# VCO.net
KiCad netlist of a schematic drawn in EAGLE
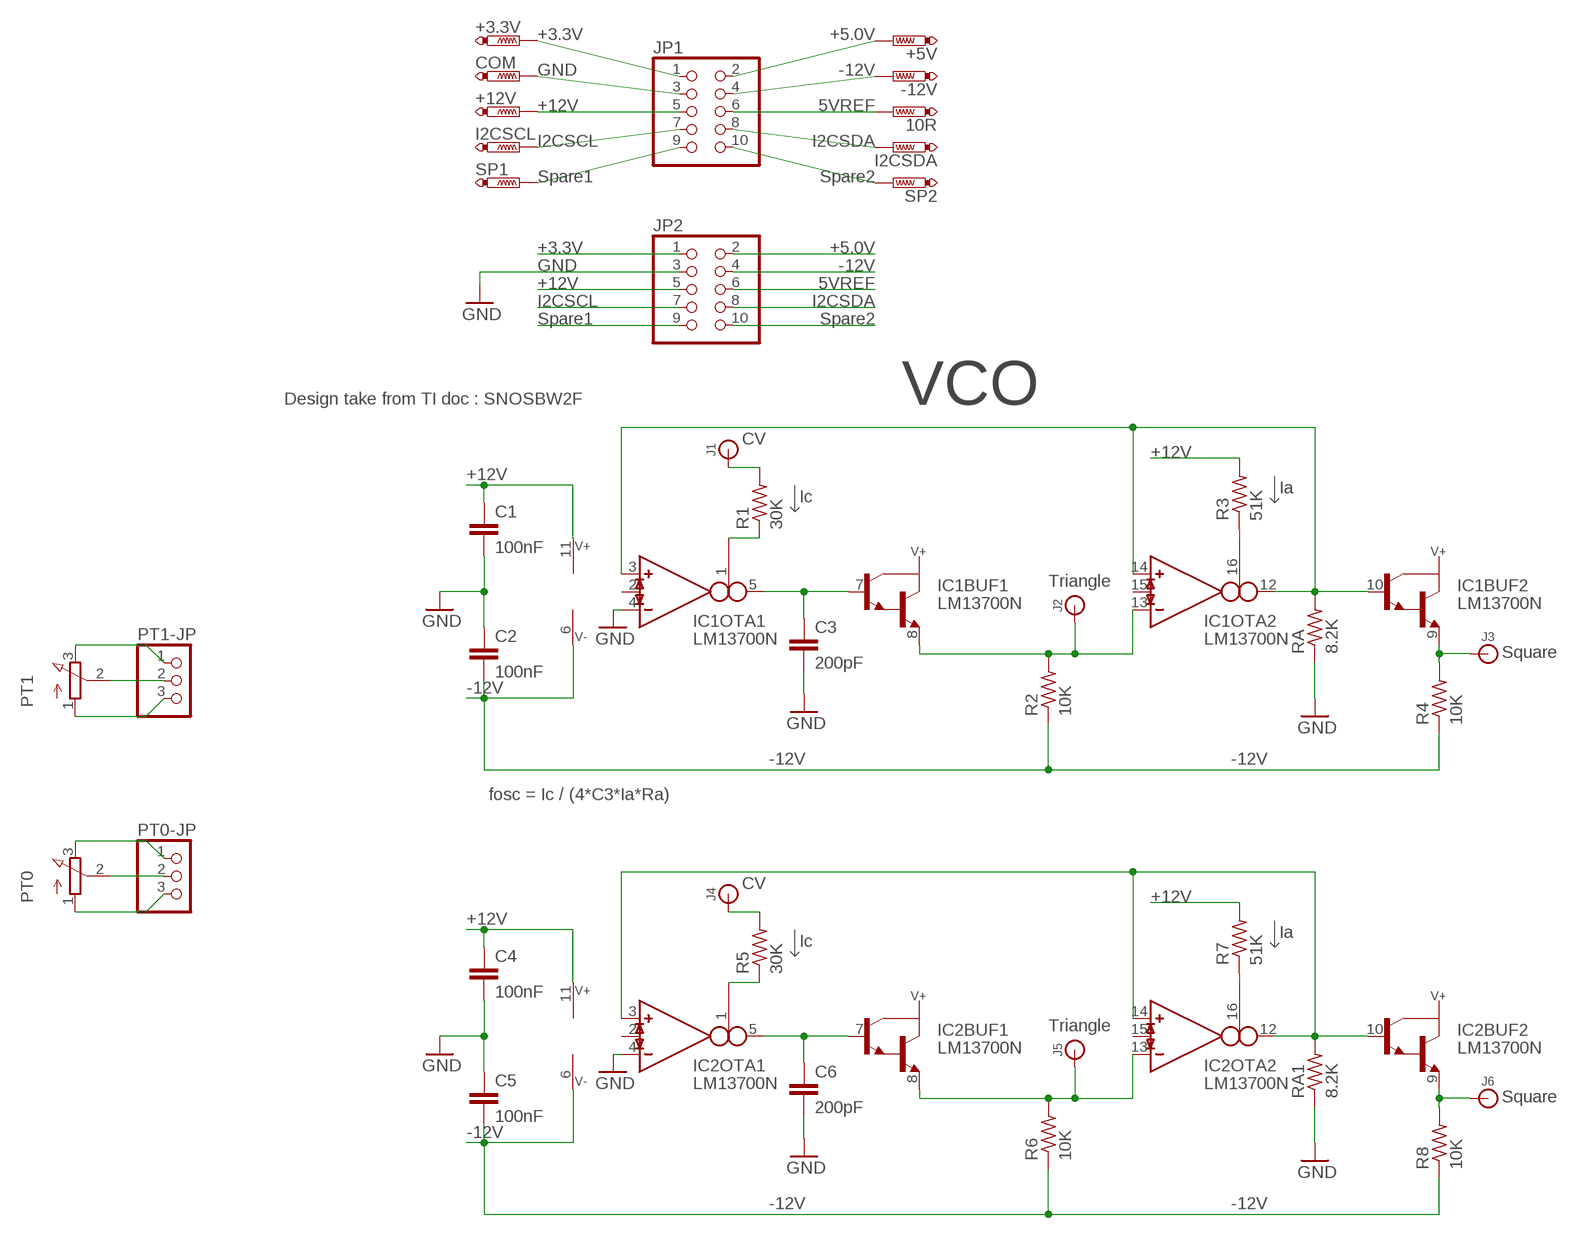
[diagram p0: schematic, sheet 1]

(export (version "E")
  (design (tool "Eeschema 10.0.6"))
  (components
    (comp (ref "+3.3V")
      (value "PTR1B1,27")
      (footprint "eagle-import:B1,27")
      (libsource (lib "eagle-import") (part "PTR1B1,27"))
    )
    (comp (ref "+5V")
      (value "PTR1B1,27")
      (footprint "eagle-import:B1,27")
      (libsource (lib "eagle-import") (part "PTR1B1,27"))
    )
    (comp (ref "+12V")
      (value "PTR1B1,27")
      (footprint "eagle-import:B1,27")
      (libsource (lib "eagle-import") (part "PTR1B1,27"))
    )
    (comp (ref "-12V")
      (value "PTR1B1,27")
      (footprint "eagle-import:B1,27")
      (libsource (lib "eagle-import") (part "PTR1B1,27"))
    )
    (comp (ref "10R")
      (value "PTR1B1,27")
      (footprint "eagle-import:B1,27")
      (libsource (lib "eagle-import") (part "PTR1B1,27"))
    )
    (comp (ref "C1")
      (value "100nF")
      (footprint "eagle-import:C5B2.5")
      (libsource (lib "eagle-import") (part "C5/2.5"))
    )
    (comp (ref "C2")
      (value "100nF")
      (footprint "eagle-import:C5B2.5")
      (libsource (lib "eagle-import") (part "C5/2.5"))
    )
    (comp (ref "C3")
      (value "200pF")
      (footprint "eagle-import:C5B2.5")
      (libsource (lib "eagle-import") (part "C5/2.5"))
    )
    (comp (ref "C4")
      (value "100nF")
      (footprint "eagle-import:C5B2.5")
      (libsource (lib "eagle-import") (part "C5/2.5"))
    )
    (comp (ref "C5")
      (value "100nF")
      (footprint "eagle-import:C5B2.5")
      (libsource (lib "eagle-import") (part "C5/2.5"))
    )
    (comp (ref "C6")
      (value "200pF")
      (footprint "eagle-import:C5B2.5")
      (libsource (lib "eagle-import") (part "C5/2.5"))
    )
    (comp (ref "COM")
      (value "PTR1B1,27")
      (footprint "eagle-import:B1,27")
      (libsource (lib "eagle-import") (part "PTR1B1,27"))
    )
    (comp (ref "I2CSCL")
      (value "PTR1B1,27")
      (footprint "eagle-import:B1,27")
      (libsource (lib "eagle-import") (part "PTR1B1,27"))
    )
    (comp (ref "I2CSDA")
      (value "PTR1B1,27")
      (footprint "eagle-import:B1,27")
      (libsource (lib "eagle-import") (part "PTR1B1,27"))
    )
    (comp (ref "IC1")
      (value "LM13700N")
      (footprint "eagle-import:DIL16")
      (libsource (lib "eagle-import") (part "LM13700N"))
    )
    (comp (ref "IC2")
      (value "LM13700N")
      (footprint "eagle-import:DIL16")
      (libsource (lib "eagle-import") (part "LM13700N"))
    )
    (comp (ref "J1")
      (value "BANANA_CONN")
      (footprint "eagle-import:BANANA_CONN")
      (libsource (lib "eagle-import") (part "BANANA_CONN"))
    )
    (comp (ref "J2")
      (value "BANANA_CONN")
      (footprint "eagle-import:BANANA_CONN")
      (libsource (lib "eagle-import") (part "BANANA_CONN"))
    )
    (comp (ref "J3")
      (value "BANANA_CONN")
      (footprint "eagle-import:BANANA_CONN")
      (libsource (lib "eagle-import") (part "BANANA_CONN"))
    )
    (comp (ref "J4")
      (value "BANANA_CONN")
      (footprint "eagle-import:BANANA_CONN")
      (libsource (lib "eagle-import") (part "BANANA_CONN"))
    )
    (comp (ref "J5")
      (value "BANANA_CONN")
      (footprint "eagle-import:BANANA_CONN")
      (libsource (lib "eagle-import") (part "BANANA_CONN"))
    )
    (comp (ref "J6")
      (value "BANANA_CONN")
      (footprint "eagle-import:BANANA_CONN")
      (libsource (lib "eagle-import") (part "BANANA_CONN"))
    )
    (comp (ref "JP1")
      (value "PINHD-2X5/90")
      (footprint "eagle-import:2X05_90")
      (libsource (lib "eagle-import") (part "PINHD-2X5/90"))
    )
    (comp (ref "JP2")
      (value "PINHD-2X5/90")
      (footprint "eagle-import:2X05_90")
      (libsource (lib "eagle-import") (part "PINHD-2X5/90"))
    )
    (comp (ref "PT0")
      (value "3RP/1610N")
      (footprint "eagle-import:3RP_1610N")
      (libsource (lib "eagle-import") (part "3RP/1610N"))
    )
    (comp (ref "PT0-JP")
      (value "PINHD-1X3")
      (footprint "eagle-import:1X03")
      (libsource (lib "eagle-import") (part "PINHD-1X3"))
    )
    (comp (ref "PT1")
      (value "3RP/1610N")
      (footprint "eagle-import:3RP_1610N")
      (libsource (lib "eagle-import") (part "3RP/1610N"))
    )
    (comp (ref "PT1-JP")
      (value "PINHD-1X3")
      (footprint "eagle-import:1X03")
      (libsource (lib "eagle-import") (part "PINHD-1X3"))
    )
    (comp (ref "R1")
      (value "30K")
      (footprint "eagle-import:0207_10")
      (libsource (lib "eagle-import") (part "R-US_0207/10"))
    )
    (comp (ref "R2")
      (value "10K")
      (footprint "eagle-import:0207_10")
      (libsource (lib "eagle-import") (part "R-US_0207/10"))
    )
    (comp (ref "R3")
      (value "51K")
      (footprint "eagle-import:0207_10")
      (libsource (lib "eagle-import") (part "R-US_0207/10"))
    )
    (comp (ref "R4")
      (value "10K")
      (footprint "eagle-import:0207_10")
      (libsource (lib "eagle-import") (part "R-US_0207/10"))
    )
    (comp (ref "R5")
      (value "30K")
      (footprint "eagle-import:0207_10")
      (libsource (lib "eagle-import") (part "R-US_0207/10"))
    )
    (comp (ref "R6")
      (value "10K")
      (footprint "eagle-import:0207_10")
      (libsource (lib "eagle-import") (part "R-US_0207/10"))
    )
    (comp (ref "R7")
      (value "51K")
      (footprint "eagle-import:0207_10")
      (libsource (lib "eagle-import") (part "R-US_0207/10"))
    )
    (comp (ref "R8")
      (value "10K")
      (footprint "eagle-import:0207_10")
      (libsource (lib "eagle-import") (part "R-US_0207/10"))
    )
    (comp (ref "RA")
      (value "8.2K")
      (footprint "eagle-import:0207_10")
      (libsource (lib "eagle-import") (part "R-US_0207/10"))
    )
    (comp (ref "RA1")
      (value "8.2K")
      (footprint "eagle-import:0207_10")
      (libsource (lib "eagle-import") (part "R-US_0207/10"))
    )
    (comp (ref "SP1")
      (value "PTR1B1,27")
      (footprint "eagle-import:B1,27")
      (libsource (lib "eagle-import") (part "PTR1B1,27"))
    )
    (comp (ref "SP2")
      (value "PTR1B1,27")
      (footprint "eagle-import:B1,27")
      (libsource (lib "eagle-import") (part "PTR1B1,27"))
    )
  )
  (nets
    (net (code "1") (name "/+3.3V") (class "Default")
      (node (ref "+3.3V") (pin "TP") (pinfunction "TP_TP") (pintype "input"))
      (node (ref "JP1") (pin "1") (pinfunction "1_1") (pintype "passive"))
      (node (ref "JP2") (pin "1") (pinfunction "1_1") (pintype "passive"))
    )
    (net (code "2") (name "/+5.0V") (class "Default")
      (node (ref "+5V") (pin "TP") (pinfunction "TP_TP") (pintype "input"))
      (node (ref "JP1") (pin "2") (pinfunction "2_2") (pintype "passive"))
      (node (ref "JP2") (pin "2") (pinfunction "2_2") (pintype "passive"))
    )
    (net (code "3") (name "/+12V") (class "Default")
      (node (ref "+12V") (pin "TP") (pinfunction "TP_TP") (pintype "input"))
      (node (ref "C1") (pin "1") (pinfunction "1_1") (pintype "passive"))
      (node (ref "C4") (pin "1") (pinfunction "1_1") (pintype "passive"))
      (node (ref "IC1") (pin "11") (pinfunction "V+_11") (pintype "power_in"))
      (node (ref "IC2") (pin "11") (pinfunction "V+_11") (pintype "power_in"))
      (node (ref "JP1") (pin "5") (pinfunction "5_5") (pintype "passive"))
      (node (ref "JP2") (pin "5") (pinfunction "5_5") (pintype "passive"))
      (node (ref "R3") (pin "2") (pinfunction "2_2") (pintype "passive"))
      (node (ref "R7") (pin "2") (pinfunction "2_2") (pintype "passive"))
    )
    (net (code "4") (name "/-12V") (class "Default")
      (node (ref "-12V") (pin "TP") (pinfunction "TP_TP") (pintype "input"))
      (node (ref "C2") (pin "2") (pinfunction "2_2") (pintype "passive"))
      (node (ref "C5") (pin "2") (pinfunction "2_2") (pintype "passive"))
      (node (ref "IC1") (pin "6") (pinfunction "V-_6") (pintype "power_in"))
      (node (ref "IC2") (pin "6") (pinfunction "V-_6") (pintype "power_in"))
      (node (ref "JP1") (pin "4") (pinfunction "4_4") (pintype "passive"))
      (node (ref "JP2") (pin "4") (pinfunction "4_4") (pintype "passive"))
      (node (ref "R2") (pin "1") (pinfunction "1_1") (pintype "passive"))
      (node (ref "R4") (pin "1") (pinfunction "1_1") (pintype "passive"))
      (node (ref "R6") (pin "1") (pinfunction "1_1") (pintype "passive"))
      (node (ref "R8") (pin "1") (pinfunction "1_1") (pintype "passive"))
    )
    (net (code "5") (name "/5VREF") (class "Default")
      (node (ref "10R") (pin "TP") (pinfunction "TP_TP") (pintype "input"))
      (node (ref "JP1") (pin "6") (pinfunction "6_6") (pintype "passive"))
      (node (ref "JP2") (pin "6") (pinfunction "6_6") (pintype "passive"))
    )
    (net (code "6") (name "/I2CSCL") (class "Default")
      (node (ref "I2CSCL") (pin "TP") (pinfunction "TP_TP") (pintype "input"))
      (node (ref "JP1") (pin "7") (pinfunction "7_7") (pintype "passive"))
      (node (ref "JP2") (pin "7") (pinfunction "7_7") (pintype "passive"))
    )
    (net (code "7") (name "/I2CSDA") (class "Default")
      (node (ref "I2CSDA") (pin "TP") (pinfunction "TP_TP") (pintype "input"))
      (node (ref "JP1") (pin "8") (pinfunction "8_8") (pintype "passive"))
      (node (ref "JP2") (pin "8") (pinfunction "8_8") (pintype "passive"))
    )
    (net (code "8") (name "/SPARE1") (class "Default")
      (node (ref "JP1") (pin "9") (pinfunction "9_9") (pintype "passive"))
      (node (ref "JP2") (pin "9") (pinfunction "9_9") (pintype "passive"))
      (node (ref "SP1") (pin "TP") (pinfunction "TP_TP") (pintype "input"))
    )
    (net (code "9") (name "/SPARE2") (class "Default")
      (node (ref "JP1") (pin "10") (pinfunction "10_10") (pintype "passive"))
      (node (ref "JP2") (pin "10") (pinfunction "10_10") (pintype "passive"))
      (node (ref "SP2") (pin "TP") (pinfunction "TP_TP") (pintype "input"))
    )
    (net (code "10") (name "GND") (class "Default")
      (node (ref "C1") (pin "2") (pinfunction "2_2") (pintype "passive"))
      (node (ref "C2") (pin "1") (pinfunction "1_1") (pintype "passive"))
      (node (ref "C3") (pin "2") (pinfunction "2_2") (pintype "passive"))
      (node (ref "C4") (pin "2") (pinfunction "2_2") (pintype "passive"))
      (node (ref "C5") (pin "1") (pinfunction "1_1") (pintype "passive"))
      (node (ref "C6") (pin "2") (pinfunction "2_2") (pintype "passive"))
      (node (ref "COM") (pin "TP") (pinfunction "TP_TP") (pintype "input"))
      (node (ref "IC1") (pin "4") (pinfunction "IN_N_4") (pintype "input"))
      (node (ref "IC2") (pin "4") (pinfunction "IN_N_4") (pintype "input"))
      (node (ref "JP1") (pin "3") (pinfunction "3_3") (pintype "passive"))
      (node (ref "JP2") (pin "3") (pinfunction "3_3") (pintype "passive"))
      (node (ref "RA") (pin "1") (pinfunction "1_1") (pintype "passive"))
      (node (ref "RA1") (pin "1") (pinfunction "1_1") (pintype "passive"))
    )
    (net (code "11") (name "Net-(IC1A-B)") (class "Default")
      (node (ref "C3") (pin "1") (pinfunction "1_1") (pintype "passive"))
      (node (ref "IC1") (pin "5") (pinfunction "OUT_5") (pintype "output"))
      (node (ref "IC1") (pin "7") (pinfunction "B_7") (pintype "passive"))
    )
    (net (code "12") (name "Net-(IC1A-E)") (class "Default")
      (node (ref "IC1") (pin "13") (pinfunction "IN_N_13") (pintype "input"))
      (node (ref "IC1") (pin "8") (pinfunction "E_8") (pintype "passive"))
      (node (ref "J2") (pin "P$1") (pinfunction "1_P$1") (pintype "passive"))
      (node (ref "R2") (pin "2") (pinfunction "2_2") (pintype "passive"))
    )
    (net (code "13") (name "Net-(IC1B-B)") (class "Default")
      (node (ref "IC1") (pin "10") (pinfunction "B_10") (pintype "passive"))
      (node (ref "IC1") (pin "12") (pinfunction "OUT_12") (pintype "output"))
      (node (ref "IC1") (pin "14") (pinfunction "IN_P_14") (pintype "input"))
      (node (ref "IC1") (pin "3") (pinfunction "IN_P_3") (pintype "input"))
      (node (ref "RA") (pin "2") (pinfunction "2_2") (pintype "passive"))
    )
    (net (code "14") (name "Net-(IC1B-E)") (class "Default")
      (node (ref "IC1") (pin "9") (pinfunction "E_9") (pintype "passive"))
      (node (ref "J3") (pin "P$1") (pinfunction "1_P$1") (pintype "passive"))
      (node (ref "R4") (pin "2") (pinfunction "2_2") (pintype "passive"))
    )
    (net (code "15") (name "Net-(IC1C-I_BIAS)") (class "Default")
      (node (ref "IC1") (pin "1") (pinfunction "I_BIAS_1") (pintype "input"))
      (node (ref "R1") (pin "1") (pinfunction "1_1") (pintype "passive"))
    )
    (net (code "16") (name "Net-(IC1D-I_BIAS)") (class "Default")
      (node (ref "IC1") (pin "16") (pinfunction "I_BIAS_16") (pintype "input"))
      (node (ref "R3") (pin "1") (pinfunction "1_1") (pintype "passive"))
    )
    (net (code "17") (name "Net-(IC2A-B)") (class "Default")
      (node (ref "C6") (pin "1") (pinfunction "1_1") (pintype "passive"))
      (node (ref "IC2") (pin "5") (pinfunction "OUT_5") (pintype "output"))
      (node (ref "IC2") (pin "7") (pinfunction "B_7") (pintype "passive"))
    )
    (net (code "18") (name "Net-(IC2A-E)") (class "Default")
      (node (ref "IC2") (pin "13") (pinfunction "IN_N_13") (pintype "input"))
      (node (ref "IC2") (pin "8") (pinfunction "E_8") (pintype "passive"))
      (node (ref "J5") (pin "P$1") (pinfunction "1_P$1") (pintype "passive"))
      (node (ref "R6") (pin "2") (pinfunction "2_2") (pintype "passive"))
    )
    (net (code "19") (name "Net-(IC2B-B)") (class "Default")
      (node (ref "IC2") (pin "10") (pinfunction "B_10") (pintype "passive"))
      (node (ref "IC2") (pin "12") (pinfunction "OUT_12") (pintype "output"))
      (node (ref "IC2") (pin "14") (pinfunction "IN_P_14") (pintype "input"))
      (node (ref "IC2") (pin "3") (pinfunction "IN_P_3") (pintype "input"))
      (node (ref "RA1") (pin "2") (pinfunction "2_2") (pintype "passive"))
    )
    (net (code "20") (name "Net-(IC2B-E)") (class "Default")
      (node (ref "IC2") (pin "9") (pinfunction "E_9") (pintype "passive"))
      (node (ref "J6") (pin "P$1") (pinfunction "1_P$1") (pintype "passive"))
      (node (ref "R8") (pin "2") (pinfunction "2_2") (pintype "passive"))
    )
    (net (code "21") (name "Net-(IC2C-I_BIAS)") (class "Default")
      (node (ref "IC2") (pin "1") (pinfunction "I_BIAS_1") (pintype "input"))
      (node (ref "R5") (pin "1") (pinfunction "1_1") (pintype "passive"))
    )
    (net (code "22") (name "Net-(IC2D-I_BIAS)") (class "Default")
      (node (ref "IC2") (pin "16") (pinfunction "I_BIAS_16") (pintype "input"))
      (node (ref "R7") (pin "1") (pinfunction "1_1") (pintype "passive"))
    )
    (net (code "23") (name "Net-(J1-1)") (class "Default")
      (node (ref "J1") (pin "P$1") (pinfunction "1_P$1") (pintype "passive"))
      (node (ref "R1") (pin "2") (pinfunction "2_2") (pintype "passive"))
    )
    (net (code "24") (name "Net-(J4-1)") (class "Default")
      (node (ref "J4") (pin "P$1") (pinfunction "1_P$1") (pintype "passive"))
      (node (ref "R5") (pin "2") (pinfunction "2_2") (pintype "passive"))
    )
    (net (code "25") (name "Net-(PT0-A)") (class "Default")
      (node (ref "PT0") (pin "1") (pinfunction "A_1") (pintype "passive"))
      (node (ref "PT0-JP") (pin "3") (pinfunction "3_3") (pintype "passive"))
    )
    (net (code "26") (name "Net-(PT0-E)") (class "Default")
      (node (ref "PT0") (pin "3") (pinfunction "E_3") (pintype "passive"))
      (node (ref "PT0-JP") (pin "1") (pinfunction "1_1") (pintype "passive"))
    )
    (net (code "27") (name "Net-(PT0-S)") (class "Default")
      (node (ref "PT0") (pin "2") (pinfunction "S_2") (pintype "passive"))
      (node (ref "PT0-JP") (pin "2") (pinfunction "2_2") (pintype "passive"))
    )
    (net (code "28") (name "Net-(PT1-A)") (class "Default")
      (node (ref "PT1") (pin "1") (pinfunction "A_1") (pintype "passive"))
      (node (ref "PT1-JP") (pin "3") (pinfunction "3_3") (pintype "passive"))
    )
    (net (code "29") (name "Net-(PT1-E)") (class "Default")
      (node (ref "PT1") (pin "3") (pinfunction "E_3") (pintype "passive"))
      (node (ref "PT1-JP") (pin "1") (pinfunction "1_1") (pintype "passive"))
    )
    (net (code "30") (name "Net-(PT1-S)") (class "Default")
      (node (ref "PT1") (pin "2") (pinfunction "S_2") (pintype "passive"))
      (node (ref "PT1-JP") (pin "2") (pinfunction "2_2") (pintype "passive"))
    )
    (net (code "31") (name "unconnected-(IC1C-I_DIODE-Pad2)") (class "Default")
      (node (ref "IC1") (pin "2") (pinfunction "I_DIODE_2") (pintype "input"))
    )
    (net (code "32") (name "unconnected-(IC1D-I_DIODE-Pad15)") (class "Default")
      (node (ref "IC1") (pin "15") (pinfunction "I_DIODE_15") (pintype "input"))
    )
    (net (code "33") (name "unconnected-(IC2C-I_DIODE-Pad2)") (class "Default")
      (node (ref "IC2") (pin "2") (pinfunction "I_DIODE_2") (pintype "input"))
    )
    (net (code "34") (name "unconnected-(IC2D-I_DIODE-Pad15)") (class "Default")
      (node (ref "IC2") (pin "15") (pinfunction "I_DIODE_15") (pintype "input"))
    )
  )
)
